# eeZee_microSD.net
KiCad netlist of a schematic drawn in EAGLE
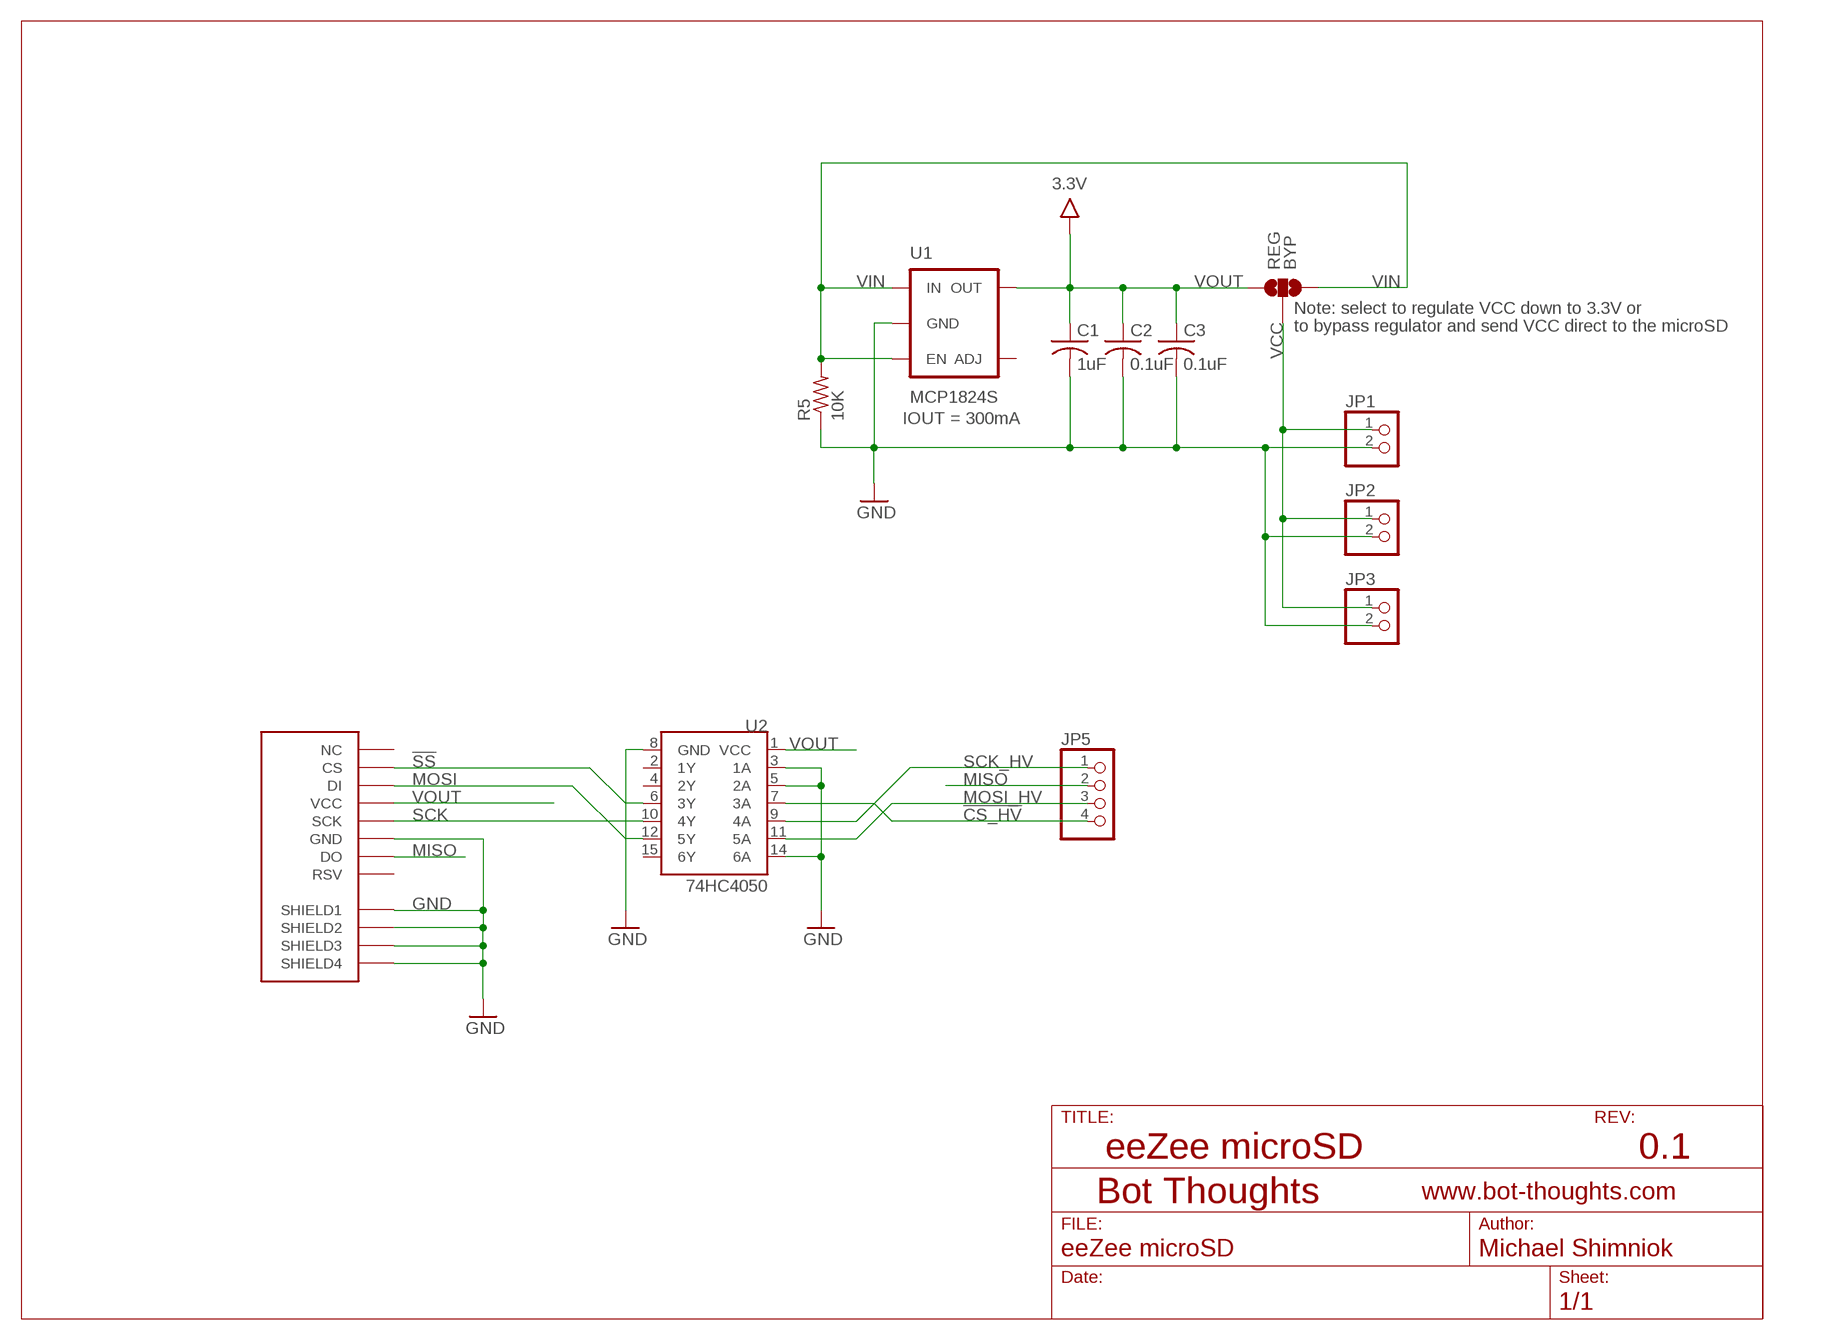
[diagram p0: schematic, sheet 1]

(export (version "E")
  (design (tool "Eeschema 10.0.6"))
  (components
    (comp (ref "C1")
      (value "1uF")
      (footprint "eagle-import:C0603")
      (fields (field (name "PARTNO") "LMK107B7105KA-T"))
      (libsource (lib "eagle-import") (part "C-USC0603"))
    )
    (comp (ref "C2")
      (value "0.1uF")
      (footprint "eagle-import:C0603")
      (fields (field (name "PARTNO") "LMK107B7105KA-T"))
      (libsource (lib "eagle-import") (part "C-USC0603"))
    )
    (comp (ref "C3")
      (value "0.1uF")
      (footprint "eagle-import:C0603")
      (fields (field (name "PARTNO") "LMK107B7105KA-T"))
      (libsource (lib "eagle-import") (part "C-USC0603"))
    )
    (comp (ref "JP1")
      (value "PINHD-1X02_2.54-S")
      (footprint "eagle-import:1X02-S")
      (libsource (lib "eagle-import") (part "PINHD-1X02_2.54-S"))
    )
    (comp (ref "JP2")
      (value "PINHD-1X02_2.54-S")
      (footprint "eagle-import:1X02-S")
      (libsource (lib "eagle-import") (part "PINHD-1X02_2.54-S"))
    )
    (comp (ref "JP3")
      (value "PINHD-1X02_2.54-S")
      (footprint "eagle-import:1X02-S")
      (libsource (lib "eagle-import") (part "PINHD-1X02_2.54-S"))
    )
    (comp (ref "JP5")
      (value "PINHD-1X04_2.54-S")
      (footprint "eagle-import:1X04-S")
      (libsource (lib "eagle-import") (part "PINHD-1X04_2.54-S"))
    )
    (comp (ref "R5")
      (value "10K")
      (footprint "eagle-import:R0603")
      (fields (field (name "PARTNO") "ERJ-3GEYJ103V"))
      (libsource (lib "eagle-import") (part "R-US_R0603"))
    )
    (comp (ref "REG")
      (value "BYP")
      (footprint "eagle-import:SJ_3")
      (libsource (lib "eagle-import") (part "SOLDERJUMPER_2WAYS"))
    )
    (comp (ref "U$1")
      (value "MICROSD_TFLASH")
      (footprint "eagle-import:TFLASH_CP-0000-086")
      (libsource (lib "eagle-import") (part "MICROSD_TFLASH"))
    )
    (comp (ref "U1")
      (value "MCP1824S")
      (footprint "eagle-import:SOT23-5")
      (fields (field (name "IOUT") "300mA") (field (name "PARTNO") "MCP1824ST-3302E/DB"))
      (libsource (lib "eagle-import") (part "MCP1824"))
    )
    (comp (ref "U2")
      (value "74HC4050")
      (footprint "eagle-import:SO016")
      (libsource (lib "eagle-import") (part "HEX_CONVERTER"))
    )
  )
  (nets
    (net (code "1") (name "/MISO") (class "Default")
      (node (ref "JP5") (pin "2") (pinfunction "2_2") (pintype "passive"))
      (node (ref "U$1") (pin "DO") (pinfunction "DO_DO") (pintype "bidirectional"))
    )
    (net (code "2") (name "/MOSI") (class "Default")
      (node (ref "U$1") (pin "DI") (pinfunction "DI_DI") (pintype "bidirectional"))
      (node (ref "U2") (pin "12") (pinfunction "5Y_12") (pintype "bidirectional"))
    )
    (net (code "3") (name "/MOSI_HV") (class "Default")
      (node (ref "JP5") (pin "3") (pinfunction "3_3") (pintype "passive"))
      (node (ref "U2") (pin "11") (pinfunction "5A_11") (pintype "bidirectional"))
    )
    (net (code "4") (name "/SCK") (class "Default")
      (node (ref "U$1") (pin "SCLK") (pinfunction "SCK_SCLK") (pintype "bidirectional"))
      (node (ref "U2") (pin "10") (pinfunction "4Y_10") (pintype "bidirectional"))
    )
    (net (code "5") (name "/SCK_HV") (class "Default")
      (node (ref "JP5") (pin "1") (pinfunction "1_1") (pintype "passive"))
      (node (ref "U2") (pin "9") (pinfunction "4A_9") (pintype "bidirectional"))
    )
    (net (code "6") (name "/VCC") (class "Default")
      (node (ref "JP1") (pin "1") (pinfunction "1_1") (pintype "passive"))
      (node (ref "JP2") (pin "1") (pinfunction "1_1") (pintype "passive"))
      (node (ref "JP3") (pin "1") (pinfunction "1_1") (pintype "passive"))
      (node (ref "REG") (pin "2") (pinfunction "2_2") (pintype "passive"))
    )
    (net (code "7") (name "/VIN") (class "Default")
      (node (ref "R5") (pin "2") (pinfunction "2_2") (pintype "passive"))
      (node (ref "REG") (pin "3") (pinfunction "3_3") (pintype "passive"))
      (node (ref "U1") (pin "1") (pinfunction "IN_1") (pintype "input"))
      (node (ref "U1") (pin "3") (pinfunction "EN_3") (pintype "input"))
    )
    (net (code "8") (name "/~{CS_HV}") (class "Default")
      (node (ref "JP5") (pin "4") (pinfunction "4_4") (pintype "passive"))
      (node (ref "U2") (pin "7") (pinfunction "3A_7") (pintype "bidirectional"))
    )
    (net (code "9") (name "/~{SS}") (class "Default")
      (node (ref "U$1") (pin "CS") (pinfunction "CS_CS") (pintype "bidirectional"))
      (node (ref "U2") (pin "6") (pinfunction "3Y_6") (pintype "bidirectional"))
    )
    (net (code "10") (name "3.3V") (class "Default")
      (node (ref "C1") (pin "1") (pinfunction "1_1") (pintype "passive"))
      (node (ref "C2") (pin "1") (pinfunction "1_1") (pintype "passive"))
      (node (ref "C3") (pin "1") (pinfunction "1_1") (pintype "passive"))
      (node (ref "REG") (pin "1") (pinfunction "1_1") (pintype "passive"))
      (node (ref "U$1") (pin "VDD") (pinfunction "VCC_VDD") (pintype "bidirectional"))
      (node (ref "U1") (pin "5") (pinfunction "OUT_5") (pintype "passive"))
      (node (ref "U2") (pin "1") (pinfunction "VCC_1") (pintype "bidirectional"))
    )
    (net (code "11") (name "GND") (class "Default")
      (node (ref "C1") (pin "2") (pinfunction "2_2") (pintype "passive"))
      (node (ref "C2") (pin "2") (pinfunction "2_2") (pintype "passive"))
      (node (ref "C3") (pin "2") (pinfunction "2_2") (pintype "passive"))
      (node (ref "JP1") (pin "2") (pinfunction "2_2") (pintype "passive"))
      (node (ref "JP2") (pin "2") (pinfunction "2_2") (pintype "passive"))
      (node (ref "JP3") (pin "2") (pinfunction "2_2") (pintype "passive"))
      (node (ref "R5") (pin "1") (pinfunction "1_1") (pintype "passive"))
      (node (ref "U$1") (pin "GND") (pinfunction "GND_GND") (pintype "bidirectional"))
      (node (ref "U$1") (pin "SHIELD1") (pinfunction "SHIELD1_SHIELD1") (pintype "bidirectional"))
      (node (ref "U$1") (pin "SHIELD2") (pinfunction "SHIELD2_SHIELD2") (pintype "bidirectional"))
      (node (ref "U$1") (pin "SHIELD3") (pinfunction "SHIELD3_SHIELD3") (pintype "bidirectional"))
      (node (ref "U$1") (pin "SHIELD4") (pinfunction "SHIELD4_SHIELD4") (pintype "bidirectional"))
      (node (ref "U1") (pin "2") (pinfunction "GND_2") (pintype "input"))
      (node (ref "U2") (pin "14") (pinfunction "6A_14") (pintype "bidirectional"))
      (node (ref "U2") (pin "3") (pinfunction "1A_3") (pintype "bidirectional"))
      (node (ref "U2") (pin "5") (pinfunction "2A_5") (pintype "bidirectional"))
      (node (ref "U2") (pin "8") (pinfunction "GND_8") (pintype "bidirectional"))
    )
    (net (code "12") (name "unconnected-(U$1-PadNC)") (class "Default")
      (node (ref "U$1") (pin "NC") (pinfunction "NC_NC") (pintype "bidirectional"))
    )
    (net (code "13") (name "unconnected-(U$1-PadRSV)") (class "Default")
      (node (ref "U$1") (pin "RSV") (pinfunction "RSV_RSV") (pintype "bidirectional"))
    )
    (net (code "14") (name "unconnected-(U1-ADJ-Pad4)") (class "Default")
      (node (ref "U1") (pin "4") (pinfunction "ADJ_4") (pintype "input"))
    )
    (net (code "15") (name "unconnected-(U2-1Y-Pad2)") (class "Default")
      (node (ref "U2") (pin "2") (pinfunction "1Y_2") (pintype "bidirectional"))
    )
    (net (code "16") (name "unconnected-(U2-2Y-Pad4)") (class "Default")
      (node (ref "U2") (pin "4") (pinfunction "2Y_4") (pintype "bidirectional"))
    )
    (net (code "17") (name "unconnected-(U2-6Y-Pad15)") (class "Default")
      (node (ref "U2") (pin "15") (pinfunction "6Y_15") (pintype "bidirectional"))
    )
  )
)
